# 3_Shutdown.net
KiCad netlist of a schematic drawn in Altium Designer
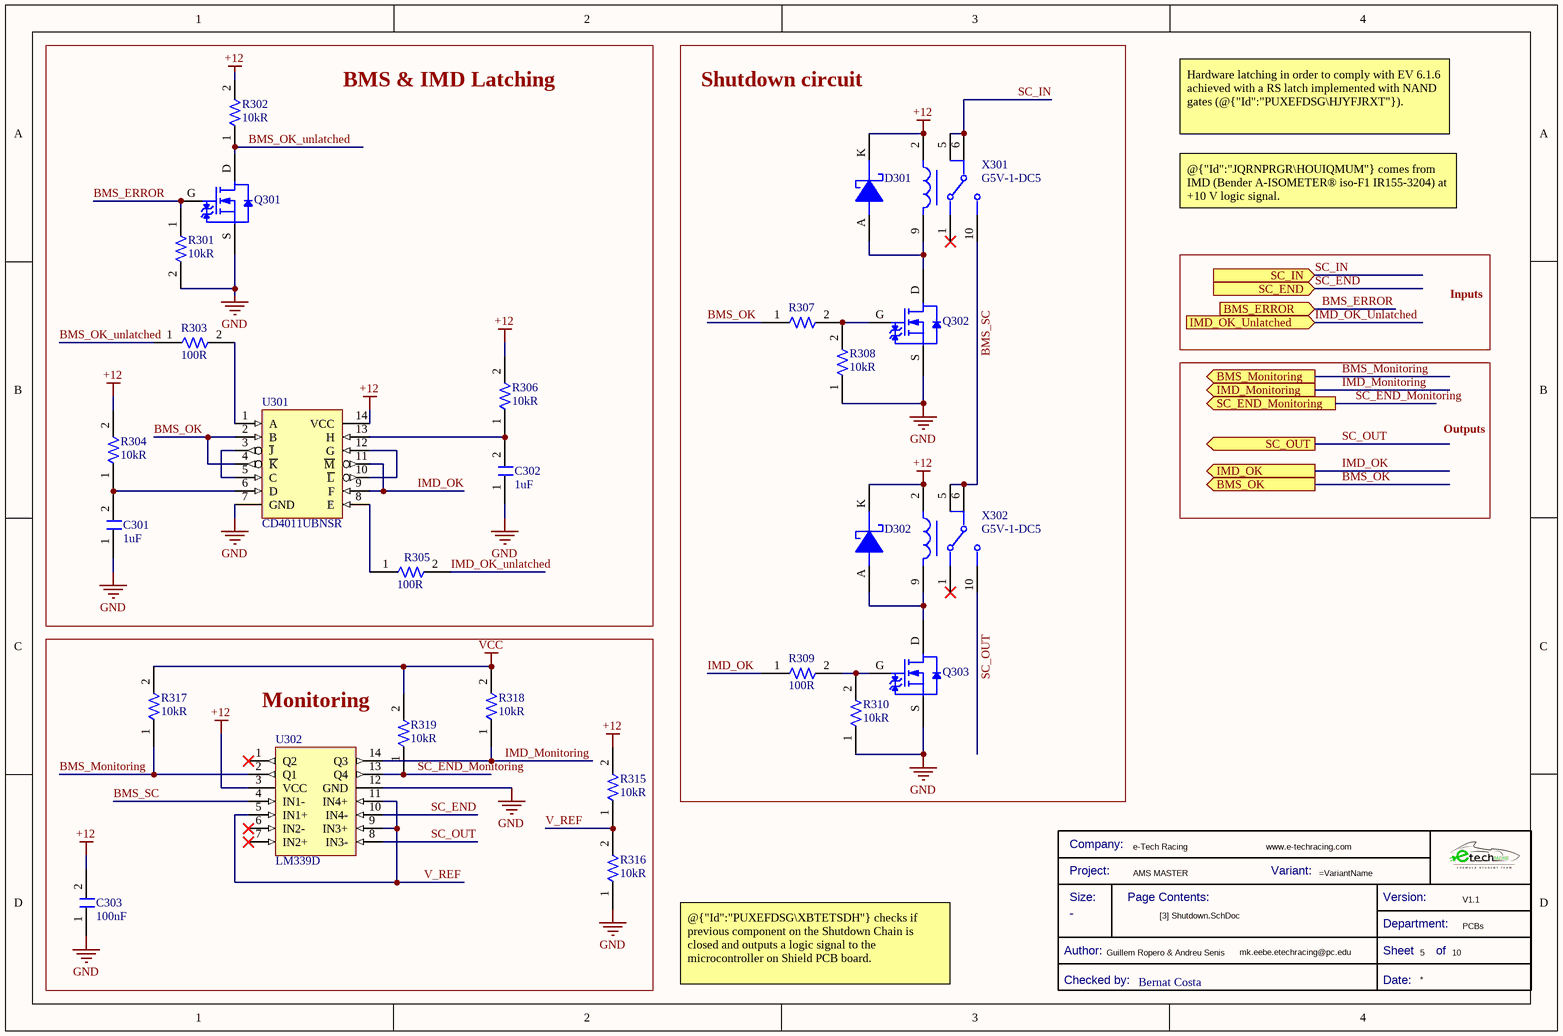
[diagram p0: [3] Shutdown.SchDoc]

(export (version "E")
  (design (tool "Eeschema 10.0.6"))
  (components
    (comp (ref "C301")
      (value "885012207103")
      (footprint "C0805FNPC-R")
      (fields
        (field (name "TOLERANCE") "10%")
        (field (name "CAPACITANCE") "1uF")
        (field (name ".CREATOR") "GP")
      )
      (libsource (lib "Passives") (part "C1u-50V-0805FNPC-X7R"))
    )
    (comp (ref "C302")
      (value "885012207103")
      (footprint "C0805FNPC-R")
      (fields
        (field (name "TOLERANCE") "10%")
        (field (name "CAPACITANCE") "1uF")
        (field (name ".CREATOR") "GP")
      )
      (libsource (lib "Passives") (part "C1u-50V-0805FNPC-X7R"))
    )
    (comp (ref "C303")
      (value "885012207098")
      (footprint "C0805FNPC-R")
      (description "Cap, 0.1ΜF, 50V, 10%, X7R, 0805")
      (fields
        (field (name "TOLERANCE") "10%")
        (field (name "CAPACITANCE") "100nF")
        (field (name ".CREATOR") "DR")
      )
      (libsource (lib "Passives") (part "C100n-50V-0805FNPC-X7R"))
    )
    (comp (ref "D301")
      (value "MBR0530")
      (footprint "DSC-SOD123")
      (description "VR=30V IF=500mA 30pF P=410mW")
      (fields (field (name ".CREATOR") "GP"))
      (libsource (lib "Filter components") (part "DSC-0.5/30-SOD123"))
    )
    (comp (ref "D302")
      (value "MBR0530")
      (footprint "DSC-SOD123")
      (description "VR=30V IF=500mA 30pF P=410mW")
      (fields (field (name ".CREATOR") "GP"))
      (libsource (lib "Filter components") (part "DSC-0.5/30-SOD123"))
    )
    (comp (ref "Q301")
      (value "CPH3455-TL-H")
      (footprint "TRT-NCH-3/35-CPH")
      (description "CPH3455-TL-H N-channel MOSFET Transistor; 3 A; 35 V; 3-Pin CPH")
      (fields (field (name "MANUFACTURER") "ON Semiconductor") (field (name ".CREATOR") "GP"))
      (libsource (lib "Semiconductor") (part "TRT-NCH-3/35-CPH"))
    )
    (comp (ref "Q302")
      (value "CPH3455-TL-H")
      (footprint "TRT-NCH-3/35-CPH")
      (description "CPH3455-TL-H N-channel MOSFET Transistor; 3 A; 35 V; 3-Pin CPH")
      (fields (field (name "MANUFACTURER") "ON Semiconductor") (field (name ".CREATOR") "GP"))
      (libsource (lib "Semiconductor") (part "TRT-NCH-3/35-CPH"))
    )
    (comp (ref "Q303")
      (value "CPH3455-TL-H")
      (footprint "TRT-NCH-3/35-CPH")
      (description "CPH3455-TL-H N-channel MOSFET Transistor; 3 A; 35 V; 3-Pin CPH")
      (fields (field (name "MANUFACTURER") "ON Semiconductor") (field (name ".CREATOR") "GP"))
      (libsource (lib "Semiconductor") (part "TRT-NCH-3/35-CPH"))
    )
    (comp (ref "R301")
      (value "CR0805-JW-103ELF")
      (footprint "R0805FTK")
      (fields
        (field (name "TOLERANCE") "5%")
        (field (name "RESISTANCE") "10kR")
        (field (name ".CREATOR") "DR")
      )
      (libsource (lib "Passives") (part "R10k-0805FTK"))
    )
    (comp (ref "R302")
      (value "CR0805-JW-103ELF")
      (footprint "R0805FTK")
      (fields
        (field (name "TOLERANCE") "5%")
        (field (name "RESISTANCE") "10kR")
        (field (name ".CREATOR") "DR")
      )
      (libsource (lib "Passives") (part "R10k-0805FTK"))
    )
    (comp (ref "R303")
      (value "CR0805-FX-1000ELF")
      (footprint "R0805FTK")
      (description "Res Thick Film 0805 100 Ohm 1% 1/8W ±100ppm/°C Molded SMD SMD Paper Tape on Plastic Reel")
      (fields
        (field (name "TOLERANCE") "1%")
        (field (name "RESISTANCE") "100R")
        (field (name ".CREATOR") "DR")
      )
      (libsource (lib "Passives") (part "R100-0805FTK"))
    )
    (comp (ref "R304")
      (value "CR0805-JW-103ELF")
      (footprint "R0805FTK")
      (fields
        (field (name "TOLERANCE") "5%")
        (field (name "RESISTANCE") "10kR")
        (field (name ".CREATOR") "DR")
      )
      (libsource (lib "Passives") (part "R10k-0805FTK"))
    )
    (comp (ref "R305")
      (value "CR0805-FX-1000ELF")
      (footprint "R0805FTK")
      (description "Res Thick Film 0805 100 Ohm 1% 1/8W ±100ppm/°C Molded SMD SMD Paper Tape on Plastic Reel")
      (fields
        (field (name "TOLERANCE") "1%")
        (field (name "RESISTANCE") "100R")
        (field (name ".CREATOR") "DR")
      )
      (libsource (lib "Passives") (part "R100-0805FTK"))
    )
    (comp (ref "R306")
      (value "CR0805-JW-103ELF")
      (footprint "R0805FTK")
      (fields
        (field (name "TOLERANCE") "5%")
        (field (name "RESISTANCE") "10kR")
        (field (name ".CREATOR") "DR")
      )
      (libsource (lib "Passives") (part "R10k-0805FTK"))
    )
    (comp (ref "R307")
      (value "CR0805-FX-1000ELF")
      (footprint "R0805FTK")
      (description "Res Thick Film 0805 100 Ohm 1% 1/8W ±100ppm/°C Molded SMD SMD Paper Tape on Plastic Reel")
      (fields (field (name "TOLERANCE") "1%") (field (name ".CREATOR") "DR"))
      (libsource (lib "Passives") (part "R100-0805FTK"))
    )
    (comp (ref "R308")
      (value "CR0805-JW-103ELF")
      (footprint "R0805FTK")
      (fields
        (field (name "TOLERANCE") "5%")
        (field (name "RESISTANCE") "10kR")
        (field (name ".CREATOR") "DR")
      )
      (libsource (lib "Passives") (part "R10k-0805FTK"))
    )
    (comp (ref "R309")
      (value "CR0805-FX-1000ELF")
      (footprint "R0805FTK")
      (description "Res Thick Film 0805 100 Ohm 1% 1/8W ±100ppm/°C Molded SMD SMD Paper Tape on Plastic Reel")
      (fields
        (field (name "TOLERANCE") "1%")
        (field (name "RESISTANCE") "100R")
        (field (name ".CREATOR") "DR")
      )
      (libsource (lib "Passives") (part "R100-0805FTK"))
    )
    (comp (ref "R310")
      (value "CR0805-JW-103ELF")
      (footprint "R0805FTK")
      (fields
        (field (name "TOLERANCE") "5%")
        (field (name "RESISTANCE") "10kR")
        (field (name ".CREATOR") "DR")
      )
      (libsource (lib "Passives") (part "R10k-0805FTK"))
    )
    (comp (ref "R315")
      (value "CR0805-JW-103ELF")
      (footprint "R0805FTK")
      (fields
        (field (name "TOLERANCE") "5%")
        (field (name "RESISTANCE") "10kR")
        (field (name ".CREATOR") "DR")
      )
      (libsource (lib "Passives") (part "R10k-0805FTK"))
    )
    (comp (ref "R316")
      (value "CR0805-JW-103ELF")
      (footprint "R0805FTK")
      (fields
        (field (name "TOLERANCE") "5%")
        (field (name "RESISTANCE") "10kR")
        (field (name ".CREATOR") "DR")
      )
      (libsource (lib "Passives") (part "R10k-0805FTK"))
    )
    (comp (ref "R317")
      (value "CR0805-JW-103ELF")
      (footprint "R0805FTK")
      (fields
        (field (name "TOLERANCE") "5%")
        (field (name "RESISTANCE") "10kR")
        (field (name ".CREATOR") "DR")
      )
      (libsource (lib "Passives") (part "R10k-0805FTK"))
    )
    (comp (ref "R318")
      (value "CR0805-JW-103ELF")
      (footprint "R0805FTK")
      (fields
        (field (name "TOLERANCE") "5%")
        (field (name "RESISTANCE") "10kR")
        (field (name ".CREATOR") "DR")
      )
      (libsource (lib "Passives") (part "R10k-0805FTK"))
    )
    (comp (ref "R319")
      (value "CR0805-JW-103ELF")
      (footprint "R0805FTK")
      (fields
        (field (name "TOLERANCE") "5%")
        (field (name "RESISTANCE") "10kR")
        (field (name ".CREATOR") "DR")
      )
      (libsource (lib "Passives") (part "R10k-0805FTK"))
    )
    (comp (ref "U301")
      (value "CD4011UBSNR")
      (footprint "ARRAY_4_NAND")
      (description "CD4011UB Cmos Quad 2-INPUT Nand")
      (fields
        (field (name "MANUFACTURER") "Texas Instruments")
        (field (name "MANUFACTURER PART NUMBER") "CD4011UBNSR")
        (field (name ".CREATOR") "DO")
      )
      (libsource (lib "Integrated circuits") (part "Array_4_NAND"))
    )
    (comp (ref "U302")
      (value "LM339D")
      (footprint "Array_4_Amp_LM339D")
      (description "Comparator Quad ±18V/36V 14-Pin SOIC Tube")
      (fields
        (field (name "MANUFACTURER") "Texas Instruments")
        (field (name "MANUFACTURER PART NUMBER") "LM339D")
        (field (name ".CREATOR") "DO")
      )
      (libsource (lib "Integrated circuits") (part "Array_4_Amp_LM339D"))
    )
    (comp (ref "X301")
      (value "G5V-1-DC5")
      (footprint "Relay_G5V-1-DC5")
      (description "Electromechanical Relay SPDT 1A 5VDC 167Ohm Through Hole")
      (fields
        (field (name "MANUFACTURER") "Omron")
        (field (name "SUPPLIER PART NUMBER 1") "G5V-1-DC5")
        (field (name ".CREATOR") "DO")
      )
      (libsource (lib "Electromechanical") (part "Relay_G5V-1-DC5"))
    )
    (comp (ref "X302")
      (value "G5V-1-DC5")
      (footprint "Relay_G5V-1-DC5")
      (description "Electromechanical Relay SPDT 1A 5VDC 167Ohm Through Hole")
      (fields
        (field (name "MANUFACTURER") "Omron")
        (field (name "SUPPLIER PART NUMBER 1") "G5V-1-DC5")
        (field (name ".CREATOR") "DO")
      )
      (libsource (lib "Electromechanical") (part "Relay_G5V-1-DC5"))
    )
  )
  (nets
    (net (code "1") (name "+12") (class "Default")
      (node (ref "C303") (pin "2") (pinfunction "2_2") (pintype "passive"))
      (node (ref "D301") (pin "K") (pinfunction "K_K") (pintype "passive"))
      (node (ref "D302") (pin "K") (pinfunction "K_K") (pintype "passive"))
      (node (ref "R302") (pin "2") (pinfunction "2_2") (pintype "passive"))
      (node (ref "R304") (pin "2") (pinfunction "2_2") (pintype "passive"))
      (node (ref "R306") (pin "2") (pinfunction "2_2") (pintype "passive"))
      (node (ref "R315") (pin "2") (pinfunction "2_2") (pintype "passive"))
      (node (ref "U301") (pin "14") (pinfunction "VCC_14") (pintype "power_in"))
      (node (ref "U302") (pin "3") (pinfunction "VCC_3") (pintype "power_in"))
      (node (ref "X301") (pin "2") (pinfunction "2_2") (pintype "passive"))
      (node (ref "X302") (pin "2") (pinfunction "2_2") (pintype "passive"))
    )
    (net (code "2") (name "/BMS_ERROR") (class "Default")
      (node (ref "Q301") (pin "G") (pinfunction "G_G") (pintype "passive"))
      (node (ref "R301") (pin "1") (pinfunction "1_1") (pintype "passive"))
    )
    (net (code "3") (name "/BMS_Monitoring") (class "Default")
      (node (ref "R317") (pin "1") (pinfunction "1_1") (pintype "passive"))
      (node (ref "U302") (pin "2") (pinfunction "Q1_2") (pintype "output"))
    )
    (net (code "4") (name "/BMS_OK") (class "Default")
      (node (ref "R307") (pin "1") (pinfunction "1_1") (pintype "passive"))
      (node (ref "U301") (pin "2") (pinfunction "B_2") (pintype "input"))
      (node (ref "U301") (pin "4") (pinfunction "~{K}_4") (pintype "output"))
    )
    (net (code "5") (name "/BMS_OK_unlatched") (class "Default")
      (node (ref "Q301") (pin "D") (pinfunction "D_D") (pintype "passive"))
      (node (ref "R302") (pin "1") (pinfunction "1_1") (pintype "passive"))
      (node (ref "R303") (pin "1") (pinfunction "1_1") (pintype "passive"))
    )
    (net (code "6") (name "/BMS_SC") (class "Default")
      (node (ref "U302") (pin "4") (pinfunction "IN1-_4") (pintype "input"))
      (node (ref "X301") (pin "10") (pinfunction "10_10") (pintype "passive"))
      (node (ref "X302") (pin "5") (pinfunction "5_5") (pintype "passive"))
      (node (ref "X302") (pin "6") (pinfunction "6_6") (pintype "passive"))
    )
    (net (code "7") (name "/IMD_Monitoring") (class "Default")
      (node (ref "R318") (pin "1") (pinfunction "1_1") (pintype "passive"))
      (node (ref "U302") (pin "14") (pinfunction "Q3_14") (pintype "output"))
    )
    (net (code "8") (name "/IMD_OK") (class "Default")
      (node (ref "R309") (pin "1") (pinfunction "1_1") (pintype "passive"))
      (node (ref "U301") (pin "11") (pinfunction "~{M}_11") (pintype "output"))
      (node (ref "U301") (pin "9") (pinfunction "F_9") (pintype "input"))
    )
    (net (code "10") (name "/IMD_OK_unlatched") (class "Default")
      (node (ref "R305") (pin "2") (pinfunction "2_2") (pintype "passive"))
    )
    (net (code "11") (name "/SC_END") (class "Default")
      (node (ref "U302") (pin "10") (pinfunction "IN4-_10") (pintype "input"))
    )
    (net (code "12") (name "/SC_END_Monitoring") (class "Default")
      (node (ref "R319") (pin "1") (pinfunction "1_1") (pintype "passive"))
      (node (ref "U302") (pin "13") (pinfunction "Q4_13") (pintype "output"))
    )
    (net (code "13") (name "/SC_IN") (class "Default")
      (node (ref "X301") (pin "5") (pinfunction "5_5") (pintype "passive"))
      (node (ref "X301") (pin "6") (pinfunction "6_6") (pintype "passive"))
    )
    (net (code "14") (name "/SC_OUT") (class "Default")
      (node (ref "U302") (pin "8") (pinfunction "IN3-_8") (pintype "input"))
      (node (ref "X302") (pin "10") (pinfunction "10_10") (pintype "passive"))
    )
    (net (code "15") (name "/V_REF") (class "Default")
      (node (ref "R315") (pin "1") (pinfunction "1_1") (pintype "passive"))
      (node (ref "R316") (pin "2") (pinfunction "2_2") (pintype "passive"))
      (node (ref "U302") (pin "11") (pinfunction "IN4+_11") (pintype "input"))
      (node (ref "U302") (pin "5") (pinfunction "IN1+_5") (pintype "input"))
      (node (ref "U302") (pin "9") (pinfunction "IN3+_9") (pintype "input"))
    )
    (net (code "16") (name "GND") (class "Default")
      (node (ref "C301") (pin "1") (pinfunction "1_1") (pintype "passive"))
      (node (ref "C302") (pin "1") (pinfunction "1_1") (pintype "passive"))
      (node (ref "C303") (pin "1") (pinfunction "1_1") (pintype "passive"))
      (node (ref "Q301") (pin "S") (pinfunction "S_S") (pintype "passive"))
      (node (ref "Q302") (pin "S") (pinfunction "S_S") (pintype "passive"))
      (node (ref "Q303") (pin "S") (pinfunction "S_S") (pintype "passive"))
      (node (ref "R301") (pin "2") (pinfunction "2_2") (pintype "passive"))
      (node (ref "R308") (pin "1") (pinfunction "1_1") (pintype "passive"))
      (node (ref "R310") (pin "1") (pinfunction "1_1") (pintype "passive"))
      (node (ref "R316") (pin "1") (pinfunction "1_1") (pintype "passive"))
      (node (ref "U301") (pin "7") (pinfunction "GND_7") (pintype "power_in"))
      (node (ref "U302") (pin "12") (pinfunction "GND_12") (pintype "power_in"))
    )
    (net (code "17") (name "Net-(D301-PadA)") (class "Default")
      (node (ref "D301") (pin "A") (pinfunction "A_A") (pintype "passive"))
      (node (ref "Q302") (pin "D") (pinfunction "D_D") (pintype "passive"))
      (node (ref "X301") (pin "9") (pinfunction "9_9") (pintype "passive"))
    )
    (net (code "18") (name "Net-(D302-PadA)") (class "Default")
      (node (ref "D302") (pin "A") (pinfunction "A_A") (pintype "passive"))
      (node (ref "Q303") (pin "D") (pinfunction "D_D") (pintype "passive"))
      (node (ref "X302") (pin "9") (pinfunction "9_9") (pintype "passive"))
    )
    (net (code "19") (name "Net-(Q302-PadG)") (class "Default")
      (node (ref "Q302") (pin "G") (pinfunction "G_G") (pintype "passive"))
      (node (ref "R307") (pin "2") (pinfunction "2_2") (pintype "passive"))
      (node (ref "R308") (pin "2") (pinfunction "2_2") (pintype "passive"))
    )
    (net (code "20") (name "Net-(Q303-PadG)") (class "Default")
      (node (ref "Q303") (pin "G") (pinfunction "G_G") (pintype "passive"))
      (node (ref "R309") (pin "2") (pinfunction "2_2") (pintype "passive"))
      (node (ref "R310") (pin "2") (pinfunction "2_2") (pintype "passive"))
    )
    (net (code "21") (name "Net-(U301-A)") (class "Default")
      (node (ref "R303") (pin "2") (pinfunction "2_2") (pintype "passive"))
      (node (ref "U301") (pin "1") (pinfunction "A_1") (pintype "input"))
    )
    (net (code "22") (name "Net-(U301-C)") (class "Default")
      (node (ref "U301") (pin "3") (pinfunction "~{J}_3") (pintype "output"))
      (node (ref "U301") (pin "5") (pinfunction "C_5") (pintype "input"))
    )
    (net (code "23") (name "Net-(U301-D)") (class "Default")
      (node (ref "C301") (pin "2") (pinfunction "2_2") (pintype "passive"))
      (node (ref "R304") (pin "1") (pinfunction "1_1") (pintype "passive"))
      (node (ref "U301") (pin "6") (pinfunction "D_6") (pintype "input"))
    )
    (net (code "24") (name "Net-(U301-E)") (class "Default")
      (node (ref "R305") (pin "1") (pinfunction "1_1") (pintype "passive"))
      (node (ref "U301") (pin "8") (pinfunction "E_8") (pintype "input"))
    )
    (net (code "25") (name "Net-(U301-G)") (class "Default")
      (node (ref "U301") (pin "10") (pinfunction "~{L}_10") (pintype "output"))
      (node (ref "U301") (pin "12") (pinfunction "G_12") (pintype "input"))
    )
    (net (code "26") (name "Net-(U301-H)") (class "Default")
      (node (ref "C302") (pin "2") (pinfunction "2_2") (pintype "passive"))
      (node (ref "R306") (pin "1") (pinfunction "1_1") (pintype "passive"))
      (node (ref "U301") (pin "13") (pinfunction "H_13") (pintype "input"))
    )
    (net (code "27") (name "VCC") (class "Default")
      (node (ref "R317") (pin "2") (pinfunction "2_2") (pintype "passive"))
      (node (ref "R318") (pin "2") (pinfunction "2_2") (pintype "passive"))
      (node (ref "R319") (pin "2") (pinfunction "2_2") (pintype "passive"))
    )
    (net (code "28") (name "unconnected-(U302-IN2+-Pad7)") (class "Default")
      (node (ref "U302") (pin "7") (pinfunction "IN2+_7") (pintype "input+no_connect"))
    )
    (net (code "29") (name "unconnected-(U302-IN2--Pad6)") (class "Default")
      (node (ref "U302") (pin "6") (pinfunction "IN2-_6") (pintype "input+no_connect"))
    )
    (net (code "30") (name "unconnected-(U302-Q2-Pad1)") (class "Default")
      (node (ref "U302") (pin "1") (pinfunction "Q2_1") (pintype "output+no_connect"))
    )
    (net (code "31") (name "unconnected-(X301-Pad1)") (class "Default")
      (node (ref "X301") (pin "1") (pinfunction "1_1") (pintype "passive+no_connect"))
    )
    (net (code "32") (name "unconnected-(X302-Pad1)") (class "Default")
      (node (ref "X302") (pin "1") (pinfunction "1_1") (pintype "passive+no_connect"))
    )
  )
)
